# EP600_SENSOR_V1_0.net
KiCad netlist of a schematic drawn in Altium Designer
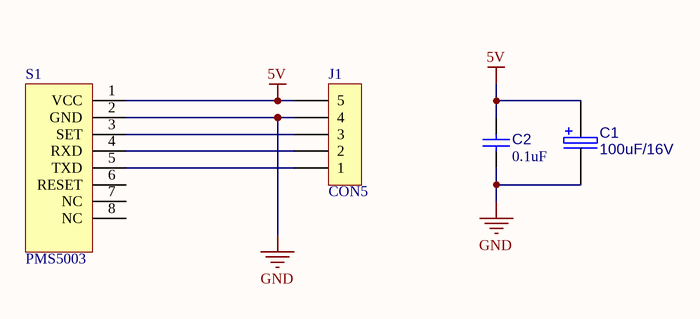
[diagram p0: EP600_SENSOR_V1.0.SchDoc]

(export (version "E")
  (design (tool "Eeschema 10.0.6"))
  (components
    (comp (ref "C1")
      (value "100uF/16V")
      (footprint "CE06150")
      (description "E-CAP")
      (libsource (lib "*") (part "ECAP"))
    )
    (comp (ref "C2")
      (value "0.1uF")
      (footprint "0805_C")
      (description "Capacitor")
      (fields (field (name "PUBLISHER") "Altium Limited"))
      (libsource (lib "EP_SENSOR_V3.0") (part "Cap"))
    )
    (comp (ref "J1")
      (value "CON5")
      (footprint "XH2.54-5PZ")
      (description "Connector")
      (libsource (lib "A09F-2-KZ_20130620") (part "CON6"))
    )
    (comp (ref "S1")
      (value "PMS5003")
      (footprint "HEADER1X8 1.27")
      (libsource (lib "MySchlib") (part "PMS5003"))
    )
  )
  (nets
    (net (code "1") (name "5V") (class "Default")
      (node (ref "C1") (pin "1") (pinfunction "+_1") (pintype "passive"))
      (node (ref "C2") (pin "2") (pinfunction "2_2") (pintype "passive"))
      (node (ref "J1") (pin "5") (pinfunction "5_5") (pintype "passive"))
      (node (ref "S1") (pin "1") (pinfunction "VCC_1") (pintype "passive"))
    )
    (net (code "2") (name "GND") (class "Default")
      (node (ref "C1") (pin "2") (pinfunction "-_2") (pintype "passive"))
      (node (ref "C2") (pin "1") (pinfunction "1_1") (pintype "passive"))
      (node (ref "J1") (pin "4") (pinfunction "4_4") (pintype "passive"))
      (node (ref "S1") (pin "2") (pinfunction "GND_2") (pintype "passive"))
    )
    (net (code "3") (name "Net-(S1-RXD)") (class "Default")
      (node (ref "J1") (pin "2") (pinfunction "2_2") (pintype "passive"))
      (node (ref "S1") (pin "4") (pinfunction "RXD_4") (pintype "passive"))
    )
    (net (code "4") (name "Net-(S1-SET)") (class "Default")
      (node (ref "J1") (pin "3") (pinfunction "3_3") (pintype "passive"))
      (node (ref "S1") (pin "3") (pinfunction "SET_3") (pintype "passive"))
    )
    (net (code "5") (name "Net-(S1-TXD)") (class "Default")
      (node (ref "J1") (pin "1") (pinfunction "1_1") (pintype "passive"))
      (node (ref "S1") (pin "5") (pinfunction "TXD_5") (pintype "passive"))
    )
    (net (code "6") (name "unconnected-(S1-NC-Pad7)") (class "Default")
      (node (ref "S1") (pin "7") (pinfunction "NC_7") (pintype "passive"))
    )
    (net (code "7") (name "unconnected-(S1-NC-Pad8)") (class "Default")
      (node (ref "S1") (pin "8") (pinfunction "NC_8") (pintype "passive"))
    )
    (net (code "8") (name "unconnected-(S1-RESET-Pad6)") (class "Default")
      (node (ref "S1") (pin "6") (pinfunction "RESET_6") (pintype "passive"))
    )
  )
)
